# beaconBoard.net
KiCad netlist of a schematic drawn in EAGLE
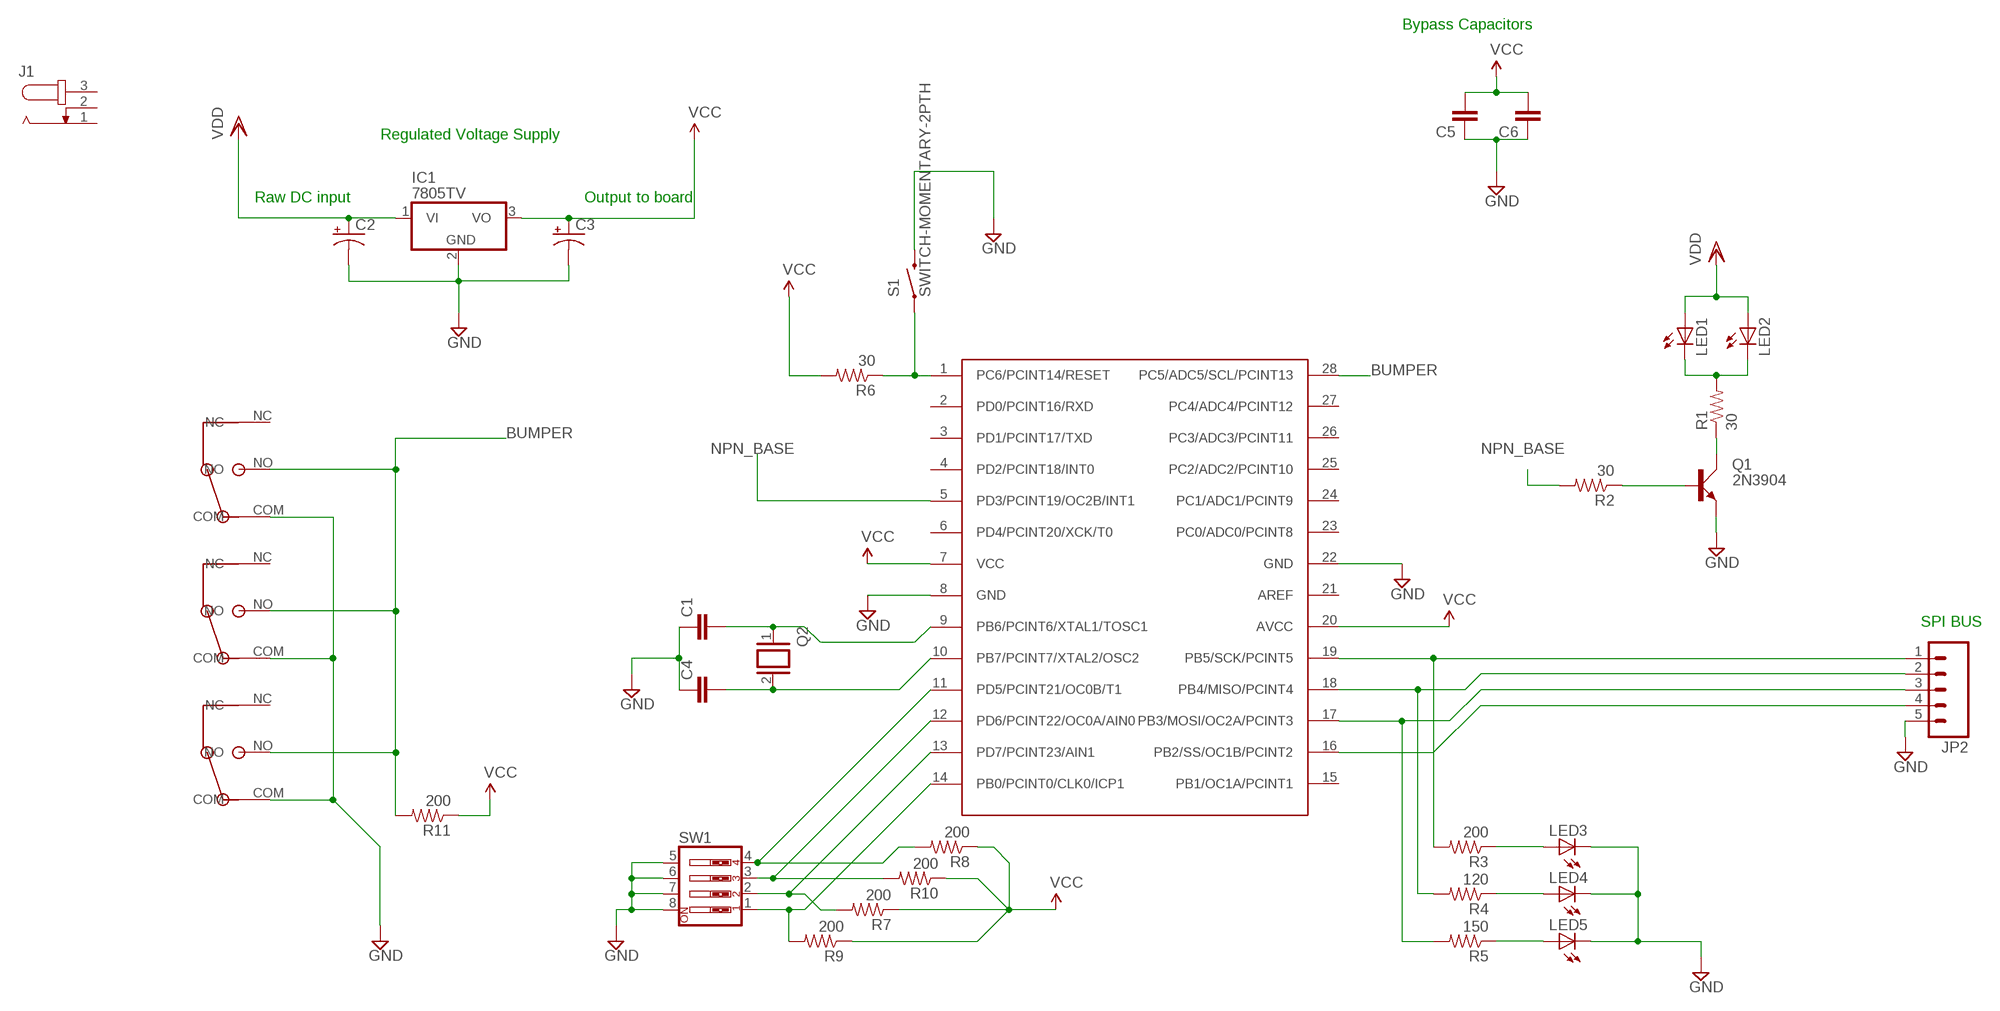
[diagram p0: schematic, sheet 1]

(export (version "E")
  (design (tool "Eeschema 10.0.6"))
  (components
    (comp (ref "C1")
      (value "CAPPTH")
      (footprint "eagle-import:CAP-PTH-SMALL")
      (libsource (lib "eagle-import") (part "CAPPTH"))
    )
    (comp (ref "C2")
      (value "CAP_POLPTH2")
      (footprint "eagle-import:CPOL-RADIAL-10UF-25V")
      (libsource (lib "eagle-import") (part "CAP_POLPTH2"))
    )
    (comp (ref "C3")
      (value "CAP_POLPTH2")
      (footprint "eagle-import:CPOL-RADIAL-10UF-25V")
      (libsource (lib "eagle-import") (part "CAP_POLPTH2"))
    )
    (comp (ref "C4")
      (value "CAPPTH")
      (footprint "eagle-import:CAP-PTH-SMALL")
      (libsource (lib "eagle-import") (part "CAPPTH"))
    )
    (comp (ref "C5")
      (value "CAPPTH")
      (footprint "eagle-import:CAP-PTH-SMALL")
      (libsource (lib "eagle-import") (part "CAPPTH"))
    )
    (comp (ref "C6")
      (value "CAPPTH")
      (footprint "eagle-import:CAP-PTH-SMALL")
      (libsource (lib "eagle-import") (part "CAPPTH"))
    )
    (comp (ref "IC1")
      (value "7805TV")
      (footprint "eagle-import:TO220V")
      (libsource (lib "eagle-import") (part "78TV05"))
    )
    (comp (ref "J1")
      (value "JACK-PLUG1")
      (footprint "eagle-import:SPC4078")
      (libsource (lib "eagle-import") (part "JACK-PLUG1"))
    )
    (comp (ref "JP2")
      (value "M05LOCK_LONGPADS")
      (footprint "eagle-import:1X05_LOCK_LONGPADS")
      (libsource (lib "eagle-import") (part "M05LOCK_LONGPADS"))
    )
    (comp (ref "LED1")
      (value "LED-2AC-CP41B-WES")
      (footprint "eagle-import:CP41B")
      (libsource (lib "eagle-import") (part "LED-2AC-CP41B-WES"))
    )
    (comp (ref "LED2")
      (value "LED-2AC-CP41B-WES")
      (footprint "eagle-import:CP41B")
      (libsource (lib "eagle-import") (part "LED-2AC-CP41B-WES"))
    )
    (comp (ref "LED3")
      (value "LED5MM")
      (footprint "eagle-import:LED5MM")
      (libsource (lib "eagle-import") (part "LED5MM"))
    )
    (comp (ref "LED4")
      (value "LED5MM")
      (footprint "eagle-import:LED5MM")
      (libsource (lib "eagle-import") (part "LED5MM"))
    )
    (comp (ref "LED5")
      (value "LED5MM")
      (footprint "eagle-import:LED5MM")
      (libsource (lib "eagle-import") (part "LED5MM"))
    )
    (comp (ref "Q1")
      (value "2N3904")
      (footprint "eagle-import:TO92D")
      (libsource (lib "eagle-import") (part "2N3904"))
    )
    (comp (ref "Q2")
      (value "XTAL/S")
      (footprint "eagle-import:QS")
      (libsource (lib "eagle-import") (part "XTAL/S"))
    )
    (comp (ref "R1")
      (value "30")
      (footprint "eagle-import:AXIAL-0.4")
      (libsource (lib "eagle-import") (part "RESISTORPTH-1/4W"))
    )
    (comp (ref "R2")
      (value "30")
      (footprint "eagle-import:AXIAL-0.4")
      (libsource (lib "eagle-import") (part "RESISTORPTH-1/4W"))
    )
    (comp (ref "R3")
      (value "200")
      (footprint "eagle-import:AXIAL-0.4")
      (libsource (lib "eagle-import") (part "RESISTORPTH-1/4W"))
    )
    (comp (ref "R4")
      (value "120")
      (footprint "eagle-import:AXIAL-0.4")
      (libsource (lib "eagle-import") (part "RESISTORPTH-1/4W"))
    )
    (comp (ref "R5")
      (value "150")
      (footprint "eagle-import:AXIAL-0.4")
      (libsource (lib "eagle-import") (part "RESISTORPTH-1/4W"))
    )
    (comp (ref "R6")
      (value "30")
      (footprint "eagle-import:AXIAL-0.4")
      (libsource (lib "eagle-import") (part "RESISTORPTH-1/4W"))
    )
    (comp (ref "R7")
      (value "200")
      (footprint "eagle-import:AXIAL-0.4")
      (libsource (lib "eagle-import") (part "RESISTORPTH-1/4W"))
    )
    (comp (ref "R8")
      (value "200")
      (footprint "eagle-import:AXIAL-0.4")
      (libsource (lib "eagle-import") (part "RESISTORPTH-1/4W"))
    )
    (comp (ref "R9")
      (value "200")
      (footprint "eagle-import:AXIAL-0.4")
      (libsource (lib "eagle-import") (part "RESISTORPTH-1/4W"))
    )
    (comp (ref "R10")
      (value "200")
      (footprint "eagle-import:AXIAL-0.4")
      (libsource (lib "eagle-import") (part "RESISTORPTH-1/4W"))
    )
    (comp (ref "R11")
      (value "200")
      (footprint "eagle-import:AXIAL-0.4")
      (libsource (lib "eagle-import") (part "RESISTORPTH-1/4W"))
    )
    (comp (ref "S1")
      (value "SWITCH-MOMENTARY-2PTH")
      (footprint "eagle-import:TACTILE-PTH")
      (libsource (lib "eagle-import") (part "SWITCH-MOMENTARY-2PTH"))
    )
    (comp (ref "SW1")
      (value "SW_DIP-4")
      (footprint "eagle-import:EDG-04")
      (libsource (lib "eagle-import") (part "SW_DIP-4"))
    )
    (comp (ref "U$1")
      (value "DF2-L")
      (footprint "eagle-import:D2F-L")
      (libsource (lib "eagle-import") (part "DF2-L"))
    )
    (comp (ref "U$2")
      (value "DF2-L")
      (footprint "eagle-import:D2F-L")
      (libsource (lib "eagle-import") (part "DF2-L"))
    )
    (comp (ref "U$3")
      (value "DF2-L")
      (footprint "eagle-import:D2F-L")
      (libsource (lib "eagle-import") (part "DF2-L"))
    )
    (comp (ref "U$4")
      (value "ATMEGA328")
      (footprint "eagle-import:DIL28-3")
      (libsource (lib "eagle-import") (part "ATMEGA328"))
    )
  )
  (nets
    (net (code "1") (name "/BUMPER") (class "Default")
      (node (ref "R11") (pin "P$2") (pinfunction "2_P$2") (pintype "passive"))
      (node (ref "U$1") (pin "NO") (pinfunction "NO_NO") (pintype "bidirectional"))
      (node (ref "U$2") (pin "NO") (pinfunction "NO_NO") (pintype "bidirectional"))
      (node (ref "U$3") (pin "NO") (pinfunction "NO_NO") (pintype "bidirectional"))
      (node (ref "U$4") (pin "28") (pinfunction "PC5/ADC5/SCL/PCINT13_28") (pintype "bidirectional"))
    )
    (net (code "2") (name "/NPN_BASE") (class "Default")
      (node (ref "R2") (pin "P$2") (pinfunction "2_P$2") (pintype "passive"))
      (node (ref "U$4") (pin "5") (pinfunction "PD3/PCINT19/OC2B/INT1_5") (pintype "bidirectional"))
    )
    (net (code "3") (name "GND") (class "Default")
      (node (ref "C1") (pin "1") (pinfunction "1_1") (pintype "passive"))
      (node (ref "C2") (pin "2") (pinfunction "-_2") (pintype "passive"))
      (node (ref "C3") (pin "2") (pinfunction "-_2") (pintype "passive"))
      (node (ref "C4") (pin "1") (pinfunction "1_1") (pintype "passive"))
      (node (ref "C5") (pin "1") (pinfunction "1_1") (pintype "passive"))
      (node (ref "C6") (pin "1") (pinfunction "1_1") (pintype "passive"))
      (node (ref "IC1") (pin "2") (pinfunction "GND_2") (pintype "passive"))
      (node (ref "JP2") (pin "5") (pinfunction "5_5") (pintype "passive"))
      (node (ref "LED3") (pin "K") (pinfunction "C_K") (pintype "passive"))
      (node (ref "LED4") (pin "K") (pinfunction "C_K") (pintype "passive"))
      (node (ref "LED5") (pin "K") (pinfunction "C_K") (pintype "passive"))
      (node (ref "Q1") (pin "E") (pinfunction "E_E") (pintype "passive"))
      (node (ref "S1") (pin "3") (pinfunction "2_3") (pintype "passive"))
      (node (ref "SW1") (pin "5") (pinfunction "5_5") (pintype "passive"))
      (node (ref "SW1") (pin "6") (pinfunction "6_6") (pintype "passive"))
      (node (ref "SW1") (pin "7") (pinfunction "7_7") (pintype "passive"))
      (node (ref "SW1") (pin "8") (pinfunction "8_8") (pintype "passive"))
      (node (ref "U$1") (pin "COM") (pinfunction "COM_COM") (pintype "bidirectional"))
      (node (ref "U$2") (pin "COM") (pinfunction "COM_COM") (pintype "bidirectional"))
      (node (ref "U$3") (pin "COM") (pinfunction "COM_COM") (pintype "bidirectional"))
      (node (ref "U$4") (pin "22") (pinfunction "GND_22") (pintype "power_in"))
      (node (ref "U$4") (pin "8") (pinfunction "GND_8") (pintype "power_in"))
    )
    (net (code "4") (name "Net-(R1-1)") (class "Default")
      (node (ref "Q1") (pin "C") (pinfunction "C_C") (pintype "passive"))
      (node (ref "R1") (pin "P$1") (pinfunction "1_P$1") (pintype "passive"))
    )
    (net (code "5") (name "Net-(R1-2)") (class "Default")
      (node (ref "LED1") (pin "1") (pinfunction "C_1") (pintype "passive"))
      (node (ref "LED1") (pin "4") (pinfunction "C_4") (pintype "passive"))
      (node (ref "LED2") (pin "1") (pinfunction "C_1") (pintype "passive"))
      (node (ref "LED2") (pin "4") (pinfunction "C_4") (pintype "passive"))
      (node (ref "R1") (pin "P$2") (pinfunction "2_P$2") (pintype "passive"))
    )
    (net (code "6") (name "Net-(R2-1)") (class "Default")
      (node (ref "Q1") (pin "B") (pinfunction "B_B") (pintype "passive"))
      (node (ref "R2") (pin "P$1") (pinfunction "1_P$1") (pintype "passive"))
    )
    (net (code "7") (name "Net-(R3-1)") (class "Default")
      (node (ref "LED3") (pin "A") (pinfunction "A_A") (pintype "passive"))
      (node (ref "R3") (pin "P$1") (pinfunction "1_P$1") (pintype "passive"))
    )
    (net (code "8") (name "Net-(R3-2)") (class "Default")
      (node (ref "JP2") (pin "1") (pinfunction "1_1") (pintype "passive"))
      (node (ref "R3") (pin "P$2") (pinfunction "2_P$2") (pintype "passive"))
      (node (ref "U$4") (pin "19") (pinfunction "PB5/SCK/PCINT5_19") (pintype "bidirectional"))
    )
    (net (code "9") (name "Net-(R4-1)") (class "Default")
      (node (ref "LED4") (pin "A") (pinfunction "A_A") (pintype "passive"))
      (node (ref "R4") (pin "P$1") (pinfunction "1_P$1") (pintype "passive"))
    )
    (net (code "10") (name "Net-(R4-2)") (class "Default")
      (node (ref "JP2") (pin "2") (pinfunction "2_2") (pintype "passive"))
      (node (ref "R4") (pin "P$2") (pinfunction "2_P$2") (pintype "passive"))
      (node (ref "U$4") (pin "18") (pinfunction "PB4/MISO/PCINT4_18") (pintype "bidirectional"))
    )
    (net (code "11") (name "Net-(R5-1)") (class "Default")
      (node (ref "LED5") (pin "A") (pinfunction "A_A") (pintype "passive"))
      (node (ref "R5") (pin "P$1") (pinfunction "1_P$1") (pintype "passive"))
    )
    (net (code "12") (name "Net-(R5-2)") (class "Default")
      (node (ref "JP2") (pin "3") (pinfunction "3_3") (pintype "passive"))
      (node (ref "R5") (pin "P$2") (pinfunction "2_P$2") (pintype "passive"))
      (node (ref "U$4") (pin "17") (pinfunction "PB3/MOSI/OC2A/PCINT3_17") (pintype "bidirectional"))
    )
    (net (code "13") (name "Net-(R6-1)") (class "Default")
      (node (ref "R6") (pin "P$1") (pinfunction "1_P$1") (pintype "passive"))
      (node (ref "S1") (pin "1") (pinfunction "1_1") (pintype "passive"))
      (node (ref "U$4") (pin "1") (pinfunction "PC6/PCINT14/RESET_1") (pintype "bidirectional"))
    )
    (net (code "14") (name "Net-(R7-2)") (class "Default")
      (node (ref "R7") (pin "P$2") (pinfunction "2_P$2") (pintype "passive"))
      (node (ref "SW1") (pin "2") (pinfunction "2_2") (pintype "passive"))
      (node (ref "U$4") (pin "13") (pinfunction "PD7/PCINT23/AIN1_13") (pintype "bidirectional"))
    )
    (net (code "15") (name "Net-(R8-2)") (class "Default")
      (node (ref "R8") (pin "P$2") (pinfunction "2_P$2") (pintype "passive"))
      (node (ref "SW1") (pin "4") (pinfunction "4_4") (pintype "passive"))
      (node (ref "U$4") (pin "11") (pinfunction "PD5/PCINT21/OC0B/T1_11") (pintype "bidirectional"))
    )
    (net (code "16") (name "Net-(R9-2)") (class "Default")
      (node (ref "R9") (pin "P$2") (pinfunction "2_P$2") (pintype "passive"))
      (node (ref "SW1") (pin "1") (pinfunction "1_1") (pintype "passive"))
      (node (ref "U$4") (pin "14") (pinfunction "PB0/PCINT0/CLK0/ICP1_14") (pintype "bidirectional"))
    )
    (net (code "17") (name "Net-(R10-2)") (class "Default")
      (node (ref "R10") (pin "P$2") (pinfunction "2_P$2") (pintype "passive"))
      (node (ref "SW1") (pin "3") (pinfunction "3_3") (pintype "passive"))
      (node (ref "U$4") (pin "12") (pinfunction "PD6/PCINT22/OC0A/AIN0_12") (pintype "bidirectional"))
    )
    (net (code "18") (name "Net-(U$4-PB2{slash}SS{slash}OC1B{slash}PCINT2)") (class "Default")
      (node (ref "JP2") (pin "4") (pinfunction "4_4") (pintype "passive"))
      (node (ref "U$4") (pin "16") (pinfunction "PB2/SS/OC1B/PCINT2_16") (pintype "bidirectional"))
    )
    (net (code "19") (name "Net-(U$4-PB6{slash}PCINT6{slash}XTAL1{slash}TOSC1)") (class "Default")
      (node (ref "C1") (pin "2") (pinfunction "2_2") (pintype "passive"))
      (node (ref "Q2") (pin "1") (pinfunction "1_1") (pintype "passive"))
      (node (ref "U$4") (pin "9") (pinfunction "PB6/PCINT6/XTAL1/TOSC1_9") (pintype "bidirectional"))
    )
    (net (code "20") (name "Net-(U$4-PB7{slash}PCINT7{slash}XTAL2{slash}OSC2)") (class "Default")
      (node (ref "C4") (pin "2") (pinfunction "2_2") (pintype "passive"))
      (node (ref "Q2") (pin "2") (pinfunction "2_2") (pintype "passive"))
      (node (ref "U$4") (pin "10") (pinfunction "PB7/PCINT7/XTAL2/OSC2_10") (pintype "bidirectional"))
    )
    (net (code "21") (name "VCC") (class "Default")
      (node (ref "C3") (pin "1") (pinfunction "+_1") (pintype "passive"))
      (node (ref "C5") (pin "2") (pinfunction "2_2") (pintype "passive"))
      (node (ref "C6") (pin "2") (pinfunction "2_2") (pintype "passive"))
      (node (ref "IC1") (pin "3") (pinfunction "VO_3") (pintype "passive"))
      (node (ref "R10") (pin "P$1") (pinfunction "1_P$1") (pintype "passive"))
      (node (ref "R11") (pin "P$1") (pinfunction "1_P$1") (pintype "passive"))
      (node (ref "R6") (pin "P$2") (pinfunction "2_P$2") (pintype "passive"))
      (node (ref "R7") (pin "P$1") (pinfunction "1_P$1") (pintype "passive"))
      (node (ref "R8") (pin "P$1") (pinfunction "1_P$1") (pintype "passive"))
      (node (ref "R9") (pin "P$1") (pinfunction "1_P$1") (pintype "passive"))
      (node (ref "U$4") (pin "20") (pinfunction "AVCC_20") (pintype "bidirectional"))
      (node (ref "U$4") (pin "7") (pinfunction "VCC_7") (pintype "power_in"))
    )
    (net (code "22") (name "VDD") (class "Default")
      (node (ref "C2") (pin "1") (pinfunction "+_1") (pintype "passive"))
      (node (ref "IC1") (pin "1") (pinfunction "VI_1") (pintype "input"))
      (node (ref "LED1") (pin "2") (pinfunction "A_2") (pintype "passive"))
      (node (ref "LED1") (pin "3") (pinfunction "A_3") (pintype "passive"))
      (node (ref "LED2") (pin "2") (pinfunction "A_2") (pintype "passive"))
      (node (ref "LED2") (pin "3") (pinfunction "A_3") (pintype "passive"))
    )
    (net (code "23") (name "unconnected-(J1-Pad1)") (class "Default")
      (node (ref "J1") (pin "1") (pinfunction "1_1") (pintype "passive"))
    )
    (net (code "24") (name "unconnected-(J1-Pad2)") (class "Default")
      (node (ref "J1") (pin "2") (pinfunction "2_2") (pintype "passive"))
    )
    (net (code "25") (name "unconnected-(J1-Pad3)") (class "Default")
      (node (ref "J1") (pin "3") (pinfunction "3_3") (pintype "passive"))
    )
    (net (code "26") (name "unconnected-(U$1-PadNC)") (class "Default")
      (node (ref "U$1") (pin "NC") (pinfunction "NC_NC") (pintype "bidirectional"))
    )
    (net (code "27") (name "unconnected-(U$2-PadNC)") (class "Default")
      (node (ref "U$2") (pin "NC") (pinfunction "NC_NC") (pintype "bidirectional"))
    )
    (net (code "28") (name "unconnected-(U$3-PadNC)") (class "Default")
      (node (ref "U$3") (pin "NC") (pinfunction "NC_NC") (pintype "bidirectional"))
    )
    (net (code "29") (name "unconnected-(U$4-AREF-Pad21)") (class "Default")
      (node (ref "U$4") (pin "21") (pinfunction "AREF_21") (pintype "bidirectional"))
    )
    (net (code "30") (name "unconnected-(U$4-PB1{slash}OC1A{slash}PCINT1-Pad15)") (class "Default")
      (node (ref "U$4") (pin "15") (pinfunction "PB1/OC1A/PCINT1_15") (pintype "bidirectional"))
    )
    (net (code "31") (name "unconnected-(U$4-PC0{slash}ADC0{slash}PCINT8-Pad23)") (class "Default")
      (node (ref "U$4") (pin "23") (pinfunction "PC0/ADC0/PCINT8_23") (pintype "bidirectional"))
    )
    (net (code "32") (name "unconnected-(U$4-PC1{slash}ADC1{slash}PCINT9-Pad24)") (class "Default")
      (node (ref "U$4") (pin "24") (pinfunction "PC1/ADC1/PCINT9_24") (pintype "bidirectional"))
    )
    (net (code "33") (name "unconnected-(U$4-PC2{slash}ADC2{slash}PCINT10-Pad25)") (class "Default")
      (node (ref "U$4") (pin "25") (pinfunction "PC2/ADC2/PCINT10_25") (pintype "bidirectional"))
    )
    (net (code "34") (name "unconnected-(U$4-PC3{slash}ADC3{slash}PCINT11-Pad26)") (class "Default")
      (node (ref "U$4") (pin "26") (pinfunction "PC3/ADC3/PCINT11_26") (pintype "bidirectional"))
    )
    (net (code "35") (name "unconnected-(U$4-PC4{slash}ADC4{slash}PCINT12-Pad27)") (class "Default")
      (node (ref "U$4") (pin "27") (pinfunction "PC4/ADC4/PCINT12_27") (pintype "bidirectional"))
    )
    (net (code "36") (name "unconnected-(U$4-PD0{slash}PCINT16{slash}RXD-Pad2)") (class "Default")
      (node (ref "U$4") (pin "2") (pinfunction "PD0/PCINT16/RXD_2") (pintype "bidirectional"))
    )
    (net (code "37") (name "unconnected-(U$4-PD1{slash}PCINT17{slash}TXD-Pad3)") (class "Default")
      (node (ref "U$4") (pin "3") (pinfunction "PD1/PCINT17/TXD_3") (pintype "bidirectional"))
    )
    (net (code "38") (name "unconnected-(U$4-PD2{slash}PCINT18{slash}INT0-Pad4)") (class "Default")
      (node (ref "U$4") (pin "4") (pinfunction "PD2/PCINT18/INT0_4") (pintype "bidirectional"))
    )
    (net (code "39") (name "unconnected-(U$4-PD4{slash}PCINT20{slash}XCK{slash}T0-Pad6)") (class "Default")
      (node (ref "U$4") (pin "6") (pinfunction "PD4/PCINT20/XCK/T0_6") (pintype "bidirectional"))
    )
  )
)
